# GNSS_Antenna.net
KiCad netlist of a schematic drawn in Altium Designer
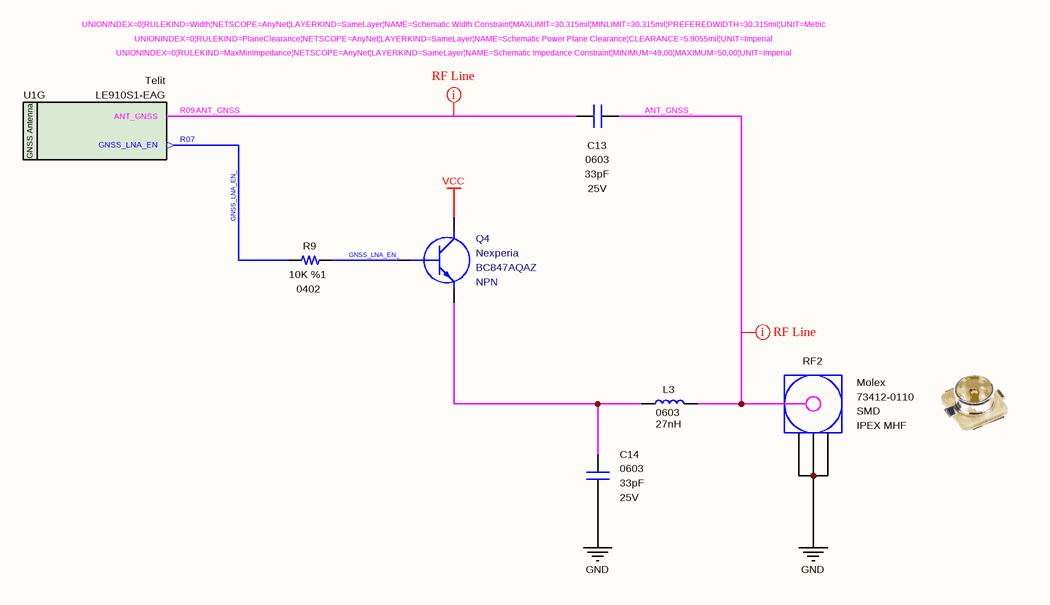
[diagram p0: GNSS Antenna.SchDoc]

(export (version "E")
  (design (tool "Eeschema 10.0.6"))
  (components
    (comp (ref "C13")
      (value "33pF")
      (footprint "CAPACITOR_0603")
      (description "Capacitor - 33pF [0603] (Ceramic)")
      (fields
        (field (name "MANUFACTURER PART NUMBER") "06033A330F4T2A")
        (field (name "TOLERANCE") "1%")
        (field (name "CASE") "0603")
        (field (name "VOLTAGE") "25V")
      )
      (libsource (lib "P101DA_Library") (part "33pF [0603-25V]"))
    )
    (comp (ref "C14")
      (value "33pF")
      (footprint "CAPACITOR_0603")
      (description "Capacitor - 33pF [0603] (Ceramic)")
      (fields
        (field (name "MANUFACTURER PART NUMBER") "06033A330F4T2A")
        (field (name "TOLERANCE") "1%")
        (field (name "CASE") "0603")
        (field (name "VOLTAGE") "25V")
      )
      (libsource (lib "P101DA_Library") (part "33pF [0603-25V]"))
    )
    (comp (ref "L3")
      (value "27nH")
      (footprint "INDUCTOR_0603")
      (description "Fixed Inductor")
      (fields
        (field (name "MANUFACTURER PART NUMBER") "LQW18AN27NJ00D")
        (field (name "TOLERANCE") "5%")
        (field (name "CASE") "0603")
      )
      (libsource (lib "P101DA_Library") (part "27nH [0603]"))
    )
    (comp (ref "Q4")
      (value "~")
      (footprint "SOT1215")
      (description "Bipolar NPN Transistors")
      (fields
        (field (name "MANUFACTURER NAME") "Nexperia")
        (field (name "MANUFACTURER PART NUMBER") "BC847AQAZ")
        (field (name "POLARITY") "NPN")
      )
      (libsource (lib "P101DA_Library") (part "BC847"))
    )
    (comp (ref "R9")
      (value "10K")
      (footprint "RESISTOR_0402")
      (description "Thick Film Resistors - SMD 1/16 W 10 Kohms 1%")
      (fields
        (field (name "CASE") "0402")
        (field (name "MANUFACTURER PART NUMBER") "CRCW040210K0FKED")
        (field (name "TOLERANCE") "%1")
      )
      (libsource (lib "P101DA_Library") (part "10K"))
    )
    (comp (ref "RF2")
      (value "~")
      (footprint "Connector_IPEX")
      (description "MOLEX   73412-0110   RF COAXIAL, MICROCOAXIAL, JACK, 50OHM")
      (fields
        (field (name "CONNECTOR TYPE") "IPEX MHF")
        (field (name "CASE") "SMD")
        (field (name "MANUFACTURER PART NUMBER") "73412-0110")
        (field (name "MANUFACTURER NAME") "Molex")
      )
      (libsource (lib "P101DA_Library") (part "IPEX MHF Connector"))
    )
    (comp (ref "U1")
      (value "LE910S1-EAG LTE GSM Module")
      (footprint "LE910 GSM Modem")
      (description "Telit LE910S1-EAG GPRS/GNSS Module")
      (fields
        (field (name "MANUFACTURER PART NUMBER") "LE910S1-EAG")
        (field (name "MANUFACTURER NAME") "Telit")
      )
      (libsource (lib "P101DA_Library") (part "IC - LE910S1-EAG"))
    )
  )
  (nets
    (net (code "1") (name "/ANT_GNSS") (class "Default")
      (node (ref "C13") (pin "2") (pinfunction "2_2") (pintype "passive"))
      (node (ref "U1") (pin "R09") (pinfunction "ANT_GNSS_R09") (pintype "passive"))
    )
    (net (code "2") (name "/ANT_GNSS_") (class "Default")
      (node (ref "C13") (pin "1") (pinfunction "1_1") (pintype "passive"))
      (node (ref "L3") (pin "2") (pinfunction "2_2") (pintype "passive"))
      (node (ref "RF2") (pin "1") (pinfunction "Signal_1") (pintype "passive"))
    )
    (net (code "3") (name "/GNSS_LNA_EN_") (class "Default")
      (node (ref "Q4") (pin "1") (pinfunction "B_1") (pintype "passive"))
      (node (ref "R9") (pin "1") (pinfunction "1_1") (pintype "passive"))
      (node (ref "R9") (pin "2") (pinfunction "2_2") (pintype "passive"))
      (node (ref "U1") (pin "R07") (pinfunction "GNSS_LNA_EN_R07") (pintype "output"))
    )
    (net (code "4") (name "GND") (class "Default")
      (node (ref "C14") (pin "1") (pinfunction "1_1") (pintype "passive"))
      (node (ref "RF2") (pin "2") (pinfunction "GND_2") (pintype "passive"))
      (node (ref "RF2") (pin "3") (pinfunction "GND_3") (pintype "passive"))
      (node (ref "RF2") (pin "4") (pinfunction "GND_4") (pintype "passive"))
    )
    (net (code "5") (name "Net-(Q4-E)") (class "Default")
      (node (ref "C14") (pin "2") (pinfunction "2_2") (pintype "passive"))
      (node (ref "L3") (pin "1") (pinfunction "1_1") (pintype "passive"))
      (node (ref "Q4") (pin "2") (pinfunction "E_2") (pintype "passive"))
    )
    (net (code "6") (name "VCC") (class "Default")
      (node (ref "Q4") (pin "3") (pinfunction "C_3") (pintype "passive"))
    )
  )
)
